# interface_com_usuario_alimentacao.net
KiCad netlist of a schematic drawn in Altium Designer
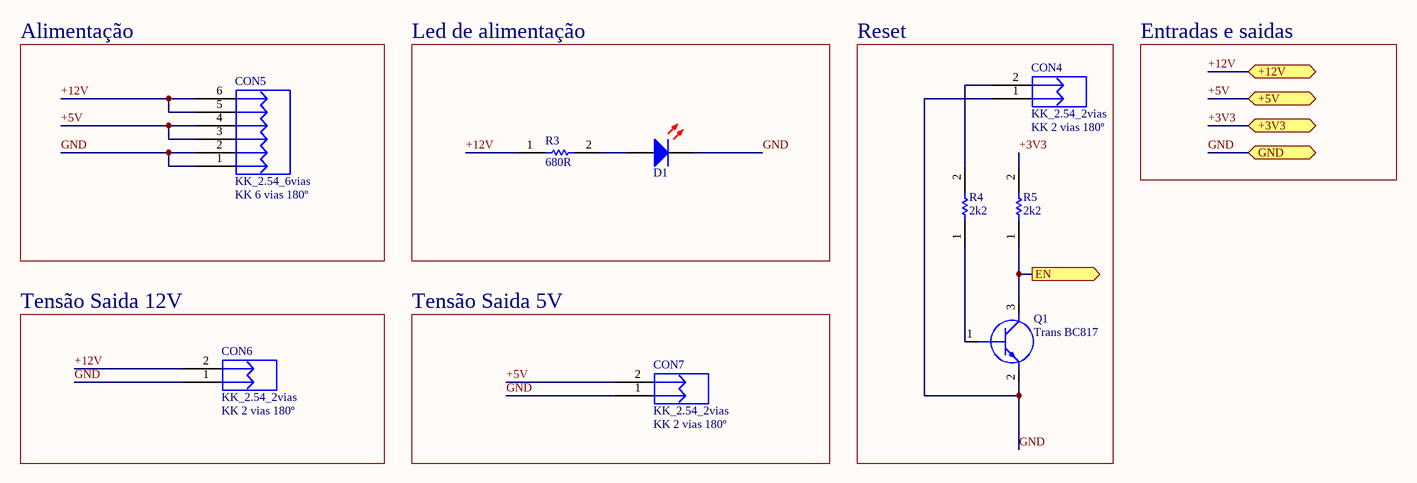
[diagram p0: interface_com_usuario_alimentacao.SchDoc]

(export (version "E")
  (design (tool "Eeschema 10.0.6"))
  (components
    (comp (ref "CON4")
      (value "KK_2.54_2vias")
      (footprint "KK_2VIAS_180º")
      (description "Conector KK 2.54mm 2 vias")
      (fields (field (name "VALOR") "KK 2 vias 180º"))
      (libsource (lib "Sinaliza玢o_Official") (part "KK_2.54_2vias"))
    )
    (comp (ref "CON5")
      (value "KK_2.54_6vias")
      (footprint "KK_6vias_180°")
      (description "Conector KK 2.54mm 6 vias")
      (fields (field (name "VALOR") "KK 6 vias 180º"))
      (libsource (lib "Sinaliza玢o_Official") (part "KK_2.54_6vias"))
    )
    (comp (ref "CON6")
      (value "KK_2.54_2vias")
      (footprint "KK_2VIAS_180º")
      (description "Conector KK 2.54mm 2 vias")
      (fields (field (name "VALOR") "KK 2 vias 180º"))
      (libsource (lib "Sinaliza玢o_Official") (part "KK_2.54_2vias"))
    )
    (comp (ref "CON7")
      (value "KK_2.54_2vias")
      (footprint "KK_2VIAS_180º")
      (description "Conector KK 2.54mm 2 vias")
      (fields (field (name "VALOR") "KK 2 vias 180º"))
      (libsource (lib "Sinaliza玢o_Official") (part "KK_2.54_2vias"))
    )
    (comp (ref "D1")
      (value "LED 3MM RED")
      (footprint "LED RED")
      (fields (field (name "MANUFACTURER") "Paralight") (field (name "MANUFACTURER PART NUMBER") "IMP585"))
      (libsource (lib "Sinaliza玢o_Official") (part "LED 3MM RED"))
    )
    (comp (ref "Q1")
      (value "Trans BC817")
      (footprint "SOT96P240X110-3N")
      (description "Transistor BJT NPN BC817-25-7-F")
      (fields
        (field (name "MANUFACTURER_PART_NUMBER") "BC817-25-7-F")
        (field (name "MOUSER PART NUMBER") "621-BC817-25-7-F")
      )
      (libsource (lib "Sinaliza玢o_Official") (part "Trans BC817"))
    )
    (comp (ref "R3")
      (value "680R")
      (footprint "RESC3216X60N")
      (description "Resistor")
      (fields
        (field (name "MANUFACTURER_PART_NUMBER") "CRCW12064K70FKEA")
        (field (name "MOUSER PART NUMBER") "71-CRCW1206-4.7K-E3")
      )
      (libsource (lib "Sinaliza玢o_Official") (part "Resistor 1206"))
    )
    (comp (ref "R4")
      (value "2k2")
      (footprint "RESC3216X60N")
      (description "Resistor")
      (fields
        (field (name "MANUFACTURER_PART_NUMBER") "CRCW12064K70FKEA")
        (field (name "MOUSER PART NUMBER") "71-CRCW1206-4.7K-E3")
      )
      (libsource (lib "Sinaliza玢o_Official") (part "Resistor 1206"))
    )
    (comp (ref "R5")
      (value "2k2")
      (footprint "RESC3216X60N")
      (description "Resistor")
      (fields
        (field (name "MANUFACTURER_PART_NUMBER") "CRCW12064K70FKEA")
        (field (name "MOUSER PART NUMBER") "71-CRCW1206-4.7K-E3")
      )
      (libsource (lib "Sinaliza玢o_Official") (part "Resistor 1206"))
    )
  )
  (nets
    (net (code "1") (name "/+3V3") (class "Default")
      (node (ref "R5") (pin "2") (pinfunction "2_2") (pintype "passive"))
    )
    (net (code "2") (name "/+5V") (class "Default")
      (node (ref "CON5") (pin "3") (pintype "passive"))
      (node (ref "CON5") (pin "4") (pintype "passive"))
      (node (ref "CON7") (pin "2") (pintype "passive"))
    )
    (net (code "3") (name "/+12V") (class "Default")
      (node (ref "CON5") (pin "5") (pintype "passive"))
      (node (ref "CON5") (pin "6") (pintype "passive"))
      (node (ref "CON6") (pin "2") (pintype "passive"))
      (node (ref "R3") (pin "1") (pinfunction "1_1") (pintype "passive"))
    )
    (net (code "4") (name "/EN") (class "Default")
      (node (ref "Q1") (pin "3") (pinfunction "C_3") (pintype "passive"))
      (node (ref "R5") (pin "1") (pinfunction "1_1") (pintype "passive"))
    )
    (net (code "5") (name "/GND") (class "Default")
      (node (ref "CON4") (pin "1") (pintype "passive"))
      (node (ref "CON5") (pin "1") (pintype "passive"))
      (node (ref "CON5") (pin "2") (pintype "passive"))
      (node (ref "CON6") (pin "1") (pintype "passive"))
      (node (ref "CON7") (pin "1") (pintype "passive"))
      (node (ref "D1") (pin "2") (pinfunction "K_2") (pintype "passive"))
      (node (ref "Q1") (pin "2") (pinfunction "E_2") (pintype "passive"))
    )
    (net (code "6") (name "Net-(CON4-Pad2)") (class "Default")
      (node (ref "CON4") (pin "2") (pintype "passive"))
      (node (ref "R4") (pin "2") (pinfunction "2_2") (pintype "passive"))
    )
    (net (code "7") (name "Net-(D1-A)") (class "Default")
      (node (ref "D1") (pin "1") (pinfunction "A_1") (pintype "passive"))
      (node (ref "R3") (pin "2") (pinfunction "2_2") (pintype "passive"))
    )
    (net (code "8") (name "Net-(Q1-B)") (class "Default")
      (node (ref "Q1") (pin "1") (pinfunction "B_1") (pintype "passive"))
      (node (ref "R4") (pin "1") (pinfunction "1_1") (pintype "passive"))
    )
  )
)
